# Expander4.net
KiCad netlist of a schematic drawn in EAGLE
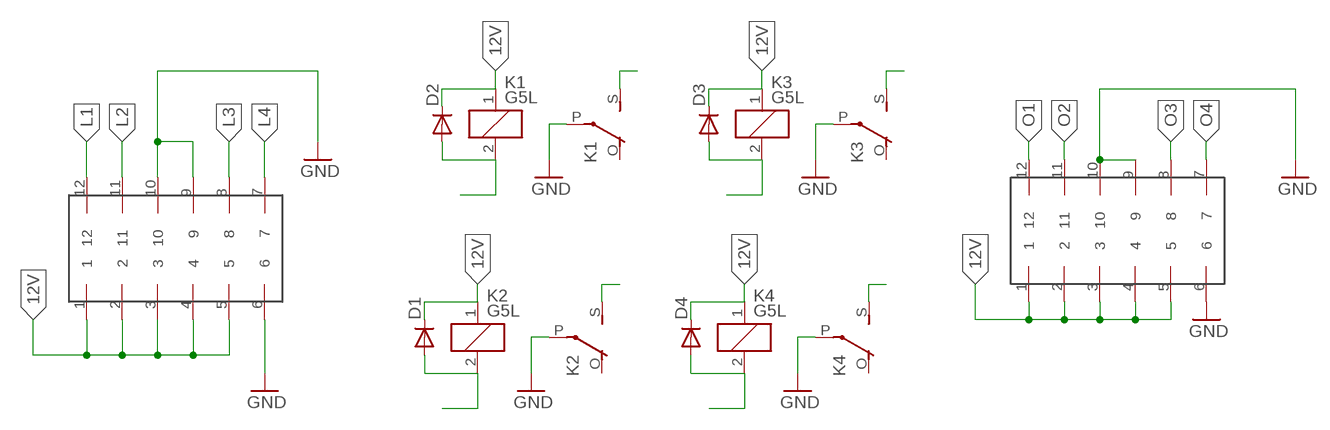
[diagram p0: schematic, sheet 1]

(export (version "E")
  (design (tool "Eeschema 10.0.6"))
  (components
    (comp (ref "D1")
      (value "DIODESMB")
      (footprint "eagle-import:SMB-DIODE")
      (libsource (lib "eagle-import") (part "DIODESMB"))
    )
    (comp (ref "D2")
      (value "DIODESMB")
      (footprint "eagle-import:SMB-DIODE")
      (libsource (lib "eagle-import") (part "DIODESMB"))
    )
    (comp (ref "D3")
      (value "DIODESMB")
      (footprint "eagle-import:SMB-DIODE")
      (libsource (lib "eagle-import") (part "DIODESMB"))
    )
    (comp (ref "D4")
      (value "DIODESMB")
      (footprint "eagle-import:SMB-DIODE")
      (libsource (lib "eagle-import") (part "DIODESMB"))
    )
    (comp (ref "IN")
      (value "MF42-10")
      (footprint "eagle-import:MF42-10")
      (libsource (lib "eagle-import") (part "MF42-10"))
    )
    (comp (ref "K1")
      (value "G5L")
      (footprint "eagle-import:G5LE")
      (fields (field (name "OC_FARNELL") "unknown") (field (name "OC_NEWARK") "unknown"))
      (libsource (lib "eagle-import") (part "G5L"))
    )
    (comp (ref "K2")
      (value "G5L")
      (footprint "eagle-import:G5LE")
      (fields (field (name "OC_FARNELL") "unknown") (field (name "OC_NEWARK") "unknown"))
      (libsource (lib "eagle-import") (part "G5L"))
    )
    (comp (ref "K3")
      (value "G5L")
      (footprint "eagle-import:G5LE")
      (fields (field (name "OC_FARNELL") "unknown") (field (name "OC_NEWARK") "unknown"))
      (libsource (lib "eagle-import") (part "G5L"))
    )
    (comp (ref "K4")
      (value "G5L")
      (footprint "eagle-import:G5LE")
      (fields (field (name "OC_FARNELL") "unknown") (field (name "OC_NEWARK") "unknown"))
      (libsource (lib "eagle-import") (part "G5L"))
    )
    (comp (ref "OUT")
      (value "MF42-10")
      (footprint "eagle-import:MF42-10")
      (libsource (lib "eagle-import") (part "MF42-10"))
    )
  )
  (nets
    (net (code "1") (name "12V") (class "Default")
      (node (ref "D1") (pin "C") (pinfunction "C_C") (pintype "passive"))
      (node (ref "D2") (pin "C") (pinfunction "C_C") (pintype "passive"))
      (node (ref "D3") (pin "C") (pinfunction "C_C") (pintype "passive"))
      (node (ref "D4") (pin "C") (pinfunction "C_C") (pintype "passive"))
      (node (ref "IN") (pin "1") (pinfunction "1_1") (pintype "bidirectional"))
      (node (ref "IN") (pin "2") (pinfunction "2_2") (pintype "bidirectional"))
      (node (ref "IN") (pin "3") (pinfunction "3_3") (pintype "bidirectional"))
      (node (ref "IN") (pin "4") (pinfunction "4_4") (pintype "bidirectional"))
      (node (ref "IN") (pin "5") (pinfunction "5_5") (pintype "bidirectional"))
      (node (ref "K1") (pin "1") (pinfunction "1_1") (pintype "passive"))
      (node (ref "K2") (pin "1") (pinfunction "1_1") (pintype "passive"))
      (node (ref "K3") (pin "1") (pinfunction "1_1") (pintype "passive"))
      (node (ref "K4") (pin "1") (pinfunction "1_1") (pintype "passive"))
      (node (ref "OUT") (pin "1") (pinfunction "1_1") (pintype "bidirectional"))
      (node (ref "OUT") (pin "2") (pinfunction "2_2") (pintype "bidirectional"))
      (node (ref "OUT") (pin "3") (pinfunction "3_3") (pintype "bidirectional"))
      (node (ref "OUT") (pin "4") (pinfunction "4_4") (pintype "bidirectional"))
      (node (ref "OUT") (pin "5") (pinfunction "5_5") (pintype "bidirectional"))
    )
    (net (code "2") (name "GND") (class "Default")
      (node (ref "IN") (pin "10") (pinfunction "10_10") (pintype "bidirectional"))
      (node (ref "IN") (pin "6") (pinfunction "6_6") (pintype "bidirectional"))
      (node (ref "IN") (pin "9") (pinfunction "9_9") (pintype "bidirectional"))
      (node (ref "K1") (pin "P") (pinfunction "P_P") (pintype "passive"))
      (node (ref "K2") (pin "P") (pinfunction "P_P") (pintype "passive"))
      (node (ref "K3") (pin "P") (pinfunction "P_P") (pintype "passive"))
      (node (ref "K4") (pin "P") (pinfunction "P_P") (pintype "passive"))
      (node (ref "OUT") (pin "10") (pinfunction "10_10") (pintype "bidirectional"))
      (node (ref "OUT") (pin "6") (pinfunction "6_6") (pintype "bidirectional"))
      (node (ref "OUT") (pin "9") (pinfunction "9_9") (pintype "bidirectional"))
    )
    (net (code "3") (name "L1") (class "Default")
      (node (ref "D2") (pin "A") (pinfunction "A_A") (pintype "passive"))
      (node (ref "IN") (pin "12") (pinfunction "12_12") (pintype "bidirectional"))
      (node (ref "K1") (pin "2") (pinfunction "2_2") (pintype "passive"))
    )
    (net (code "4") (name "L2") (class "Default")
      (node (ref "D1") (pin "A") (pinfunction "A_A") (pintype "passive"))
      (node (ref "IN") (pin "11") (pinfunction "11_11") (pintype "bidirectional"))
      (node (ref "K2") (pin "2") (pinfunction "2_2") (pintype "passive"))
    )
    (net (code "5") (name "L3") (class "Default")
      (node (ref "D3") (pin "A") (pinfunction "A_A") (pintype "passive"))
      (node (ref "IN") (pin "8") (pinfunction "8_8") (pintype "bidirectional"))
      (node (ref "K3") (pin "2") (pinfunction "2_2") (pintype "passive"))
    )
    (net (code "6") (name "L4") (class "Default")
      (node (ref "D4") (pin "A") (pinfunction "A_A") (pintype "passive"))
      (node (ref "IN") (pin "7") (pinfunction "7_7") (pintype "bidirectional"))
      (node (ref "K4") (pin "2") (pinfunction "2_2") (pintype "passive"))
    )
    (net (code "7") (name "O1") (class "Default")
      (node (ref "K1") (pin "S") (pinfunction "S_S") (pintype "passive"))
      (node (ref "OUT") (pin "12") (pinfunction "12_12") (pintype "bidirectional"))
    )
    (net (code "8") (name "O2") (class "Default")
      (node (ref "K2") (pin "S") (pinfunction "S_S") (pintype "passive"))
      (node (ref "OUT") (pin "11") (pinfunction "11_11") (pintype "bidirectional"))
    )
    (net (code "9") (name "O3") (class "Default")
      (node (ref "K3") (pin "S") (pinfunction "S_S") (pintype "passive"))
      (node (ref "OUT") (pin "8") (pinfunction "8_8") (pintype "bidirectional"))
    )
    (net (code "10") (name "O4") (class "Default")
      (node (ref "K4") (pin "S") (pinfunction "S_S") (pintype "passive"))
      (node (ref "OUT") (pin "7") (pinfunction "7_7") (pintype "bidirectional"))
    )
    (net (code "11") (name "unconnected-(K1-PadO)") (class "Default")
      (node (ref "K1") (pin "O") (pinfunction "O_O") (pintype "passive"))
    )
    (net (code "12") (name "unconnected-(K2-PadO)") (class "Default")
      (node (ref "K2") (pin "O") (pinfunction "O_O") (pintype "passive"))
    )
    (net (code "13") (name "unconnected-(K3-PadO)") (class "Default")
      (node (ref "K3") (pin "O") (pinfunction "O_O") (pintype "passive"))
    )
    (net (code "14") (name "unconnected-(K4-PadO)") (class "Default")
      (node (ref "K4") (pin "O") (pinfunction "O_O") (pintype "passive"))
    )
  )
)
